# LMAT_AMT_V2.net
KiCad netlist of a schematic drawn in Altium Designer
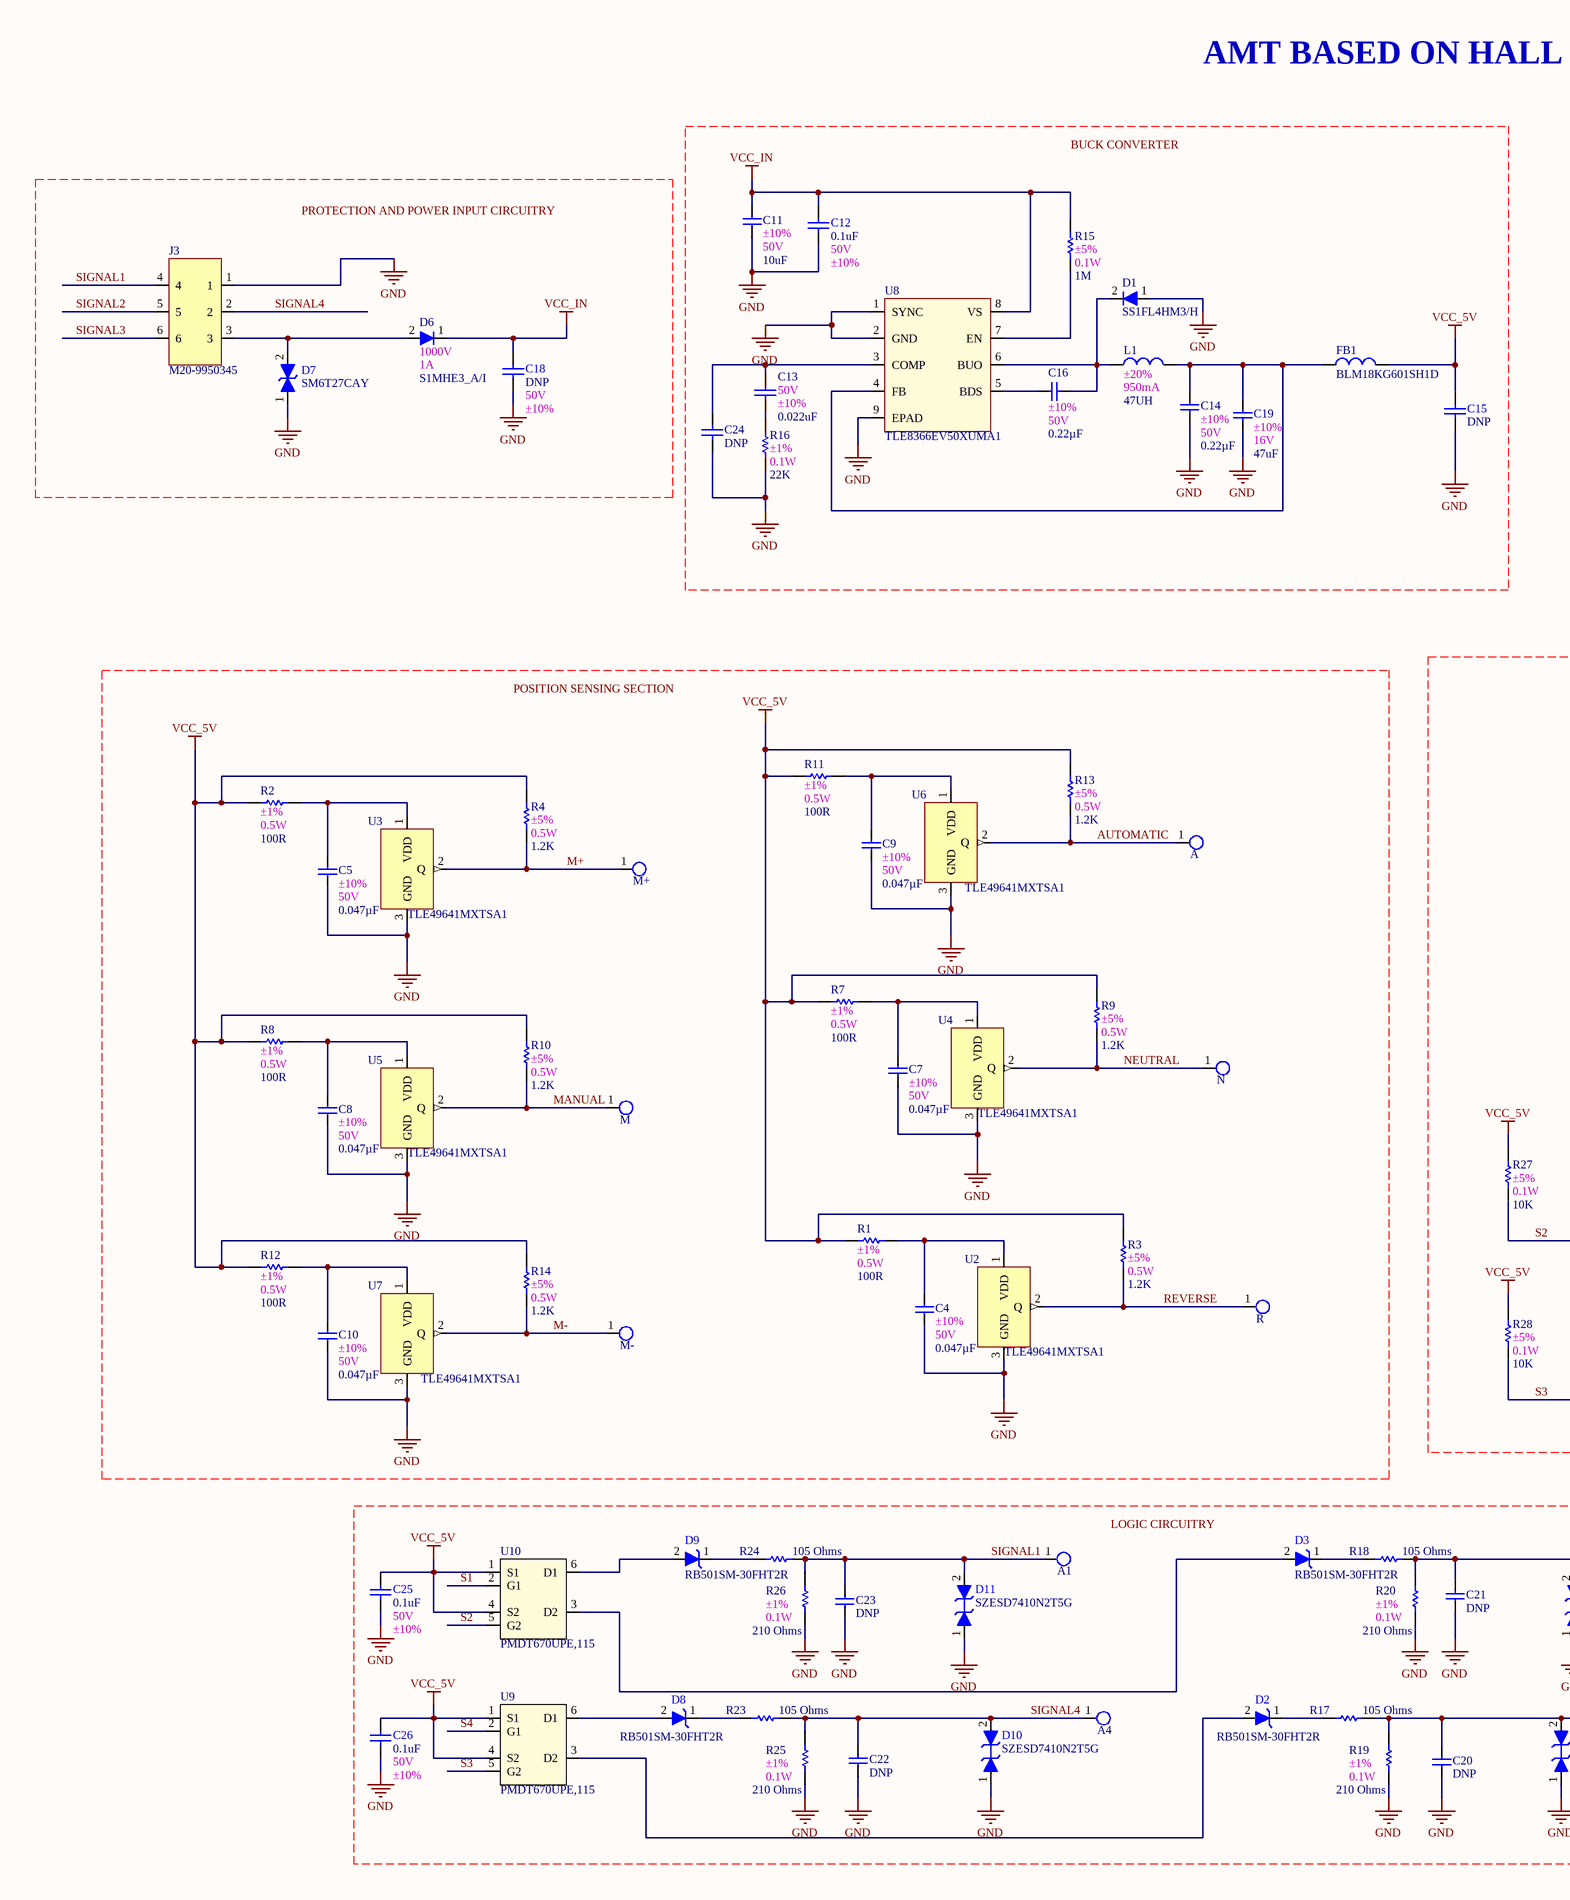
[diagram p0: LMAT_AMT_V2.SchDoc, left]
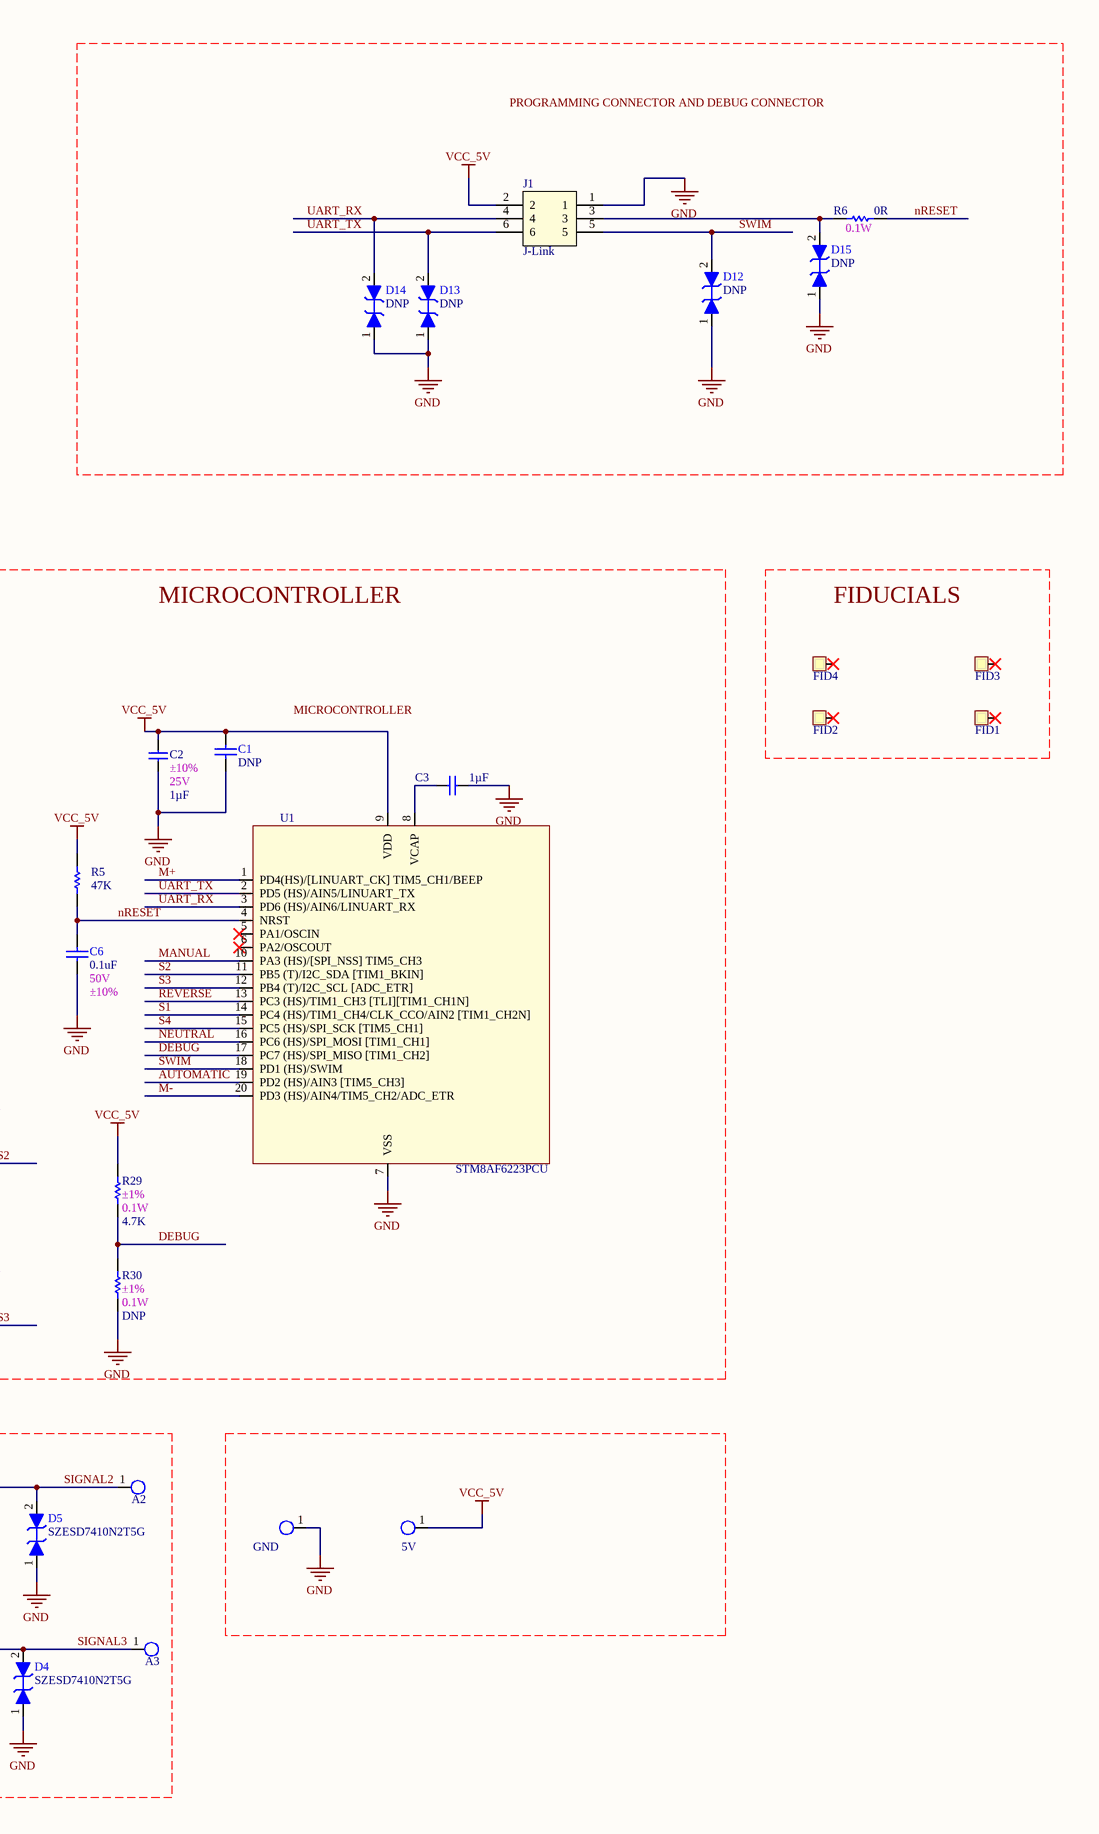
[diagram p1: LMAT_AMT_V2.SchDoc, right]

(export (version "E")
  (design (tool "Eeschema 10.0.6"))
  (components
    (comp (ref "5V")
      (value "Test Point- 35mil")
      (footprint "Integrated_Master_Library:TP_35M_DIA")
      (fields (field (name "INTERNAL PART NUMBER") "EMS-TP35MIL-S"))
      (libsource (lib "Integrated_Master_Library") (part "EMS-TP35MIL-S"))
    )
    (comp (ref "A")
      (value "Test Point- 35mil")
      (footprint "Integrated_Master_Library:TP_35M_DIA")
      (fields (field (name "INTERNAL PART NUMBER") "EMS-TP35MIL-S"))
      (libsource (lib "Integrated_Master_Library") (part "EMS-TP35MIL-S"))
    )
    (comp (ref "A1")
      (value "Test Point- 35mil")
      (footprint "Integrated_Master_Library:TP_35M_DIA")
      (fields (field (name "INTERNAL PART NUMBER") "EMS-TP35MIL-S"))
      (libsource (lib "Integrated_Master_Library") (part "EMS-TP35MIL-S"))
    )
    (comp (ref "A2")
      (value "Test Point- 35mil")
      (footprint "Integrated_Master_Library:TP_35M_DIA")
      (fields (field (name "INTERNAL PART NUMBER") "EMS-TP35MIL-S"))
      (libsource (lib "Integrated_Master_Library") (part "EMS-TP35MIL-S"))
    )
    (comp (ref "A3")
      (value "Test Point- 35mil")
      (footprint "Integrated_Master_Library:TP_35M_DIA")
      (fields (field (name "INTERNAL PART NUMBER") "EMS-TP35MIL-S"))
      (libsource (lib "Integrated_Master_Library") (part "EMS-TP35MIL-S"))
    )
    (comp (ref "A4")
      (value "Test Point- 35mil")
      (footprint "Integrated_Master_Library:TP_35M_DIA")
      (fields (field (name "INTERNAL PART NUMBER") "EMS-TP35MIL-S"))
      (libsource (lib "Integrated_Master_Library") (part "EMS-TP35MIL-S"))
    )
    (comp (ref "C1")
      (value "DNP")
      (footprint "SMDC0603")
      (description "CAP CER 0.1UF 50V 10% X7R 0603")
      (fields
        (field (name "MANUFACTURER PART NUMBER") "CGA3E2X7R1H104K080AA")
        (field (name "MANUFACTURER") "TDK Corporation")
      )
      (libsource (lib "Integrated_Master_Library") (part "ECA0U10K50V0-SC"))
    )
    (comp (ref "C2")
      (value "1µF")
      (footprint "Automobile-ML:SMDC0603")
      (description "CAP CER 1UF 25V X7R 0603")
      (fields
        (field (name "MANUFACTURER") "TDK Corporation")
        (field (name "VENDOR PART NUMBER") "445-173628-1-ND")
        (field (name "2ND AUXILIARY FIELD") "±10%")
        (field (name "1ST AUXILIARY FIELD") "25V")
      )
      (libsource (lib "Integrated_Master_Library (3)") (part "ECA1U00L25V0-SC"))
    )
    (comp (ref "C3")
      (value "1µF")
      (footprint "Automobile-ML:SMDC0603")
      (description "CAP CER 1UF 25V X7R 0603")
      (fields
        (field (name "MANUFACTURER") "TDK Corporation")
        (field (name "VENDOR PART NUMBER") "445-173628-1-ND")
      )
      (libsource (lib "Integrated_Master_Library (3)") (part "ECA1U00L25V0-SC"))
    )
    (comp (ref "C4")
      (value "0.047µF")
      (footprint "SMDC0603")
      (description "CAP CER 0.047UF 50V X7R 0603")
      (fields
        (field (name "MANUFACTURER") "TDK Corporation")
        (field (name "VENDOR PART NUMBER") "445-5664-1-ND")
        (field (name "2ND AUXILIARY FIELD") "±10%")
        (field (name "1ST AUXILIARY FIELD") "50V")
      )
      (libsource (lib "Integrated_Master_Library") (part "ECA47N0L50V-SC"))
    )
    (comp (ref "C5")
      (value "0.047µF")
      (footprint "SMDC0603")
      (description "CAP CER 0.047UF 50V X7R 0603")
      (fields
        (field (name "MANUFACTURER") "TDK Corporation")
        (field (name "VENDOR PART NUMBER") "445-5664-1-ND")
        (field (name "2ND AUXILIARY FIELD") "±10%")
        (field (name "1ST AUXILIARY FIELD") "50V")
      )
      (libsource (lib "Integrated_Master_Library") (part "ECA47N0L50V-SC"))
    )
    (comp (ref "C6")
      (value "0.1uF")
      (footprint "SMDC0603")
      (description "CAP CER 0.1UF 50V 10% X7R 0603")
      (fields
        (field (name "MANUFACTURER PART NUMBER") "CGA3E2X7R1H104K080AA")
        (field (name "MANUFACTURER") "TDK Corporation")
        (field (name "1ST AUXILIARY FIELD") "50V")
        (field (name "2ND AUXILIARY FIELD") "±10%")
      )
      (libsource (lib "Integrated_Master_Library") (part "ECA0U10K50V0-SC"))
    )
    (comp (ref "C7")
      (value "0.047µF")
      (footprint "SMDC0603")
      (description "CAP CER 0.047UF 50V X7R 0603")
      (fields
        (field (name "MANUFACTURER") "TDK Corporation")
        (field (name "VENDOR PART NUMBER") "445-5664-1-ND")
        (field (name "2ND AUXILIARY FIELD") "±10%")
        (field (name "1ST AUXILIARY FIELD") "50V")
      )
      (libsource (lib "Integrated_Master_Library") (part "ECA47N0L50V-SC"))
    )
    (comp (ref "C8")
      (value "0.047µF")
      (footprint "SMDC0603")
      (description "CAP CER 0.047UF 50V X7R 0603")
      (fields
        (field (name "MANUFACTURER") "TDK Corporation")
        (field (name "VENDOR PART NUMBER") "445-5664-1-ND")
        (field (name "2ND AUXILIARY FIELD") "±10%")
        (field (name "1ST AUXILIARY FIELD") "50V")
      )
      (libsource (lib "Integrated_Master_Library") (part "ECA47N0L50V-SC"))
    )
    (comp (ref "C9")
      (value "0.047µF")
      (footprint "SMDC0603")
      (description "CAP CER 0.047UF 50V X7R 0603")
      (fields
        (field (name "MANUFACTURER") "TDK Corporation")
        (field (name "VENDOR PART NUMBER") "445-5664-1-ND")
        (field (name "2ND AUXILIARY FIELD") "±10%")
        (field (name "1ST AUXILIARY FIELD") "50V")
      )
      (libsource (lib "Integrated_Master_Library") (part "ECA47N0L50V-SC"))
    )
    (comp (ref "C10")
      (value "0.047µF")
      (footprint "SMDC0603")
      (description "CAP CER 0.047UF 50V X7R 0603")
      (fields
        (field (name "MANUFACTURER") "TDK Corporation")
        (field (name "VENDOR PART NUMBER") "445-5664-1-ND")
        (field (name "2ND AUXILIARY FIELD") "±10%")
        (field (name "1ST AUXILIARY FIELD") "50V")
      )
      (libsource (lib "Integrated_Master_Library") (part "ECA47N0L50V-SC"))
    )
    (comp (ref "C11")
      (value "10uF")
      (footprint "SMDC1210")
      (description "CAP CER 10UF 50V X7R 1210")
      (fields
        (field (name "MANUFACTURER") "Taiyo Yuden")
        (field (name "VENDOR PART NUMBER") "587-6026-1-ND")
        (field (name "2ND AUXILIARY FIELD") "±10%")
        (field (name "1ST AUXILIARY FIELD") "50V")
      )
      (libsource (lib "Automobile-ML") (part "ECA10U0L50V0-SH"))
    )
    (comp (ref "C12")
      (value "0.1uF")
      (footprint "SMDC0603")
      (description "CAP CER 0.1UF 50V 10% X7R 0603")
      (fields
        (field (name "MANUFACTURER PART NUMBER") "CGA3E2X7R1H104K080AA")
        (field (name "MANUFACTURER") "TDK Corporation")
        (field (name "1ST AUXILIARY FIELD") "50V")
        (field (name "2ND AUXILIARY FIELD") "±10%")
      )
      (libsource (lib "Integrated_Master_Library") (part "ECA0U10K50V0-SC"))
    )
    (comp (ref "C13")
      (value "0.022uF")
      (footprint "SMDC0603")
      (description "CAP CER 0.022UF 50V 10% X7R 0603")
      (fields
        (field (name "MANUFACTURER PART NUMBER") "CGA3E2X7R1H223K080AA")
        (field (name "MANUFACTURER") "TDK Corporation")
        (field (name "1ST AUXILIARY FIELD") "50V")
        (field (name "2ND AUXILIARY FIELD") "±10%")
      )
      (libsource (lib "Integrated_Master_Library") (part "ECA0U022K50V0-SC"))
    )
    (comp (ref "C14")
      (value "0.22µF")
      (footprint "Automobile-ML:SMDC0603")
      (description "CAP CER 0.22UF 50V X7R 0603")
      (fields
        (field (name "MANUFACTURER") "Murata Electronics North America")
        (field (name "VENDOR PART NUMBER") "490-14410-1-ND")
        (field (name "2ND AUXILIARY FIELD") "±10%")
        (field (name "1ST AUXILIARY FIELD") "50V")
      )
      (libsource (lib "Integrated_Master_Library (3)") (part "ECA0U22L50V0-SC"))
    )
    (comp (ref "C15")
      (value "DNP")
      (footprint "SMDC0603")
      (description "CAP CER 0.1UF 50V 10% X7R 0603")
      (fields
        (field (name "MANUFACTURER PART NUMBER") "CGA3E2X7R1H104K080AA")
        (field (name "MANUFACTURER") "TDK Corporation")
      )
      (libsource (lib "Integrated_Master_Library") (part "ECA0U10K50V0-SC"))
    )
    (comp (ref "C16")
      (value "0.22µF")
      (footprint "SMDC0603")
      (description "CAP CER 0.22UF 50V X7R 0603")
      (fields
        (field (name "MANUFACTURER") "Murata Electronics North America")
        (field (name "VENDOR PART NUMBER") "490-14410-1-ND")
        (field (name "2ND AUXILIARY FIELD") "±10%")
        (field (name "1ST AUXILIARY FIELD") "50V")
      )
      (libsource (lib "Integrated_Master_Library") (part "ECA0U22L50V0-SC"))
    )
    (comp (ref "C18")
      (value "DNP")
      (footprint "SMDC0603")
      (description "CAP CER 0.1UF 50V 10% X7R 0603")
      (fields
        (field (name "MANUFACTURER PART NUMBER") "CGA3E2X7R1H104K080AA")
        (field (name "MANUFACTURER") "TDK Corporation")
        (field (name "1ST AUXILIARY FIELD") "50V")
        (field (name "2ND AUXILIARY FIELD") "±10%")
      )
      (libsource (lib "Integrated_Master_Library") (part "ECA0U10K50V0-SC"))
    )
    (comp (ref "C19")
      (value "47uF")
      (footprint "SMDC1210")
      (description "CAP CER 47UF 16V X6S 1210")
      (fields
        (field (name "MANUFACTURER") "Murata Electronics North America")
        (field (name "VENDOR PART NUMBER") "490-12494-1-ND")
        (field (name "2ND AUXILIARY FIELD") "±10%")
        (field (name "1ST AUXILIARY FIELD") "16V")
      )
      (libsource (lib "Automobile-ML") (part "ECA47U0L16V0-SH"))
    )
    (comp (ref "C20")
      (value "DNP")
      (footprint "SMDC0603")
      (description "CAP CER 10000PF 50V X8R 0603")
      (fields
        (field (name "MANUFACTURER") "TDK Corporation")
        (field (name "VENDOR PART NUMBER") "445-5892-1-ND")
      )
      (libsource (lib "Automobile-ML") (part "ECA0U01L50V0-SC"))
    )
    (comp (ref "C21")
      (value "DNP")
      (footprint "SMDC0603")
      (description "CAP CER 10000PF 50V X8R 0603")
      (fields
        (field (name "MANUFACTURER") "TDK Corporation")
        (field (name "VENDOR PART NUMBER") "445-5892-1-ND")
      )
      (libsource (lib "Automobile-ML") (part "ECA0U01L50V0-SC"))
    )
    (comp (ref "C22")
      (value "DNP")
      (footprint "SMDC0603")
      (description "CAP CER 10000PF 50V X8R 0603")
      (fields
        (field (name "MANUFACTURER") "TDK Corporation")
        (field (name "VENDOR PART NUMBER") "445-5892-1-ND")
      )
      (libsource (lib "Automobile-ML") (part "ECA0U01L50V0-SC"))
    )
    (comp (ref "C23")
      (value "DNP")
      (footprint "SMDC0603")
      (description "CAP CER 10000PF 50V X8R 0603")
      (fields
        (field (name "MANUFACTURER") "TDK Corporation")
        (field (name "VENDOR PART NUMBER") "445-5892-1-ND")
      )
      (libsource (lib "Automobile-ML") (part "ECA0U01L50V0-SC"))
    )
    (comp (ref "C24")
      (value "DNP")
      (footprint "SMDC0603")
      (description "CAP CER 0.022UF 50V 10% X7R 0603")
      (fields
        (field (name "MANUFACTURER PART NUMBER") "CGA3E2X7R1H223K080AA")
        (field (name "MANUFACTURER") "TDK Corporation")
      )
      (libsource (lib "Integrated_Master_Library") (part "ECA0U022K50V0-SC"))
    )
    (comp (ref "C25")
      (value "0.1uF")
      (footprint "SMDC0603")
      (description "CAP CER 0.1UF 50V 10% X7R 0603")
      (fields
        (field (name "MANUFACTURER PART NUMBER") "CGA3E2X7R1H104K080AA")
        (field (name "MANUFACTURER") "TDK Corporation")
        (field (name "1ST AUXILIARY FIELD") "50V")
        (field (name "2ND AUXILIARY FIELD") "±10%")
      )
      (libsource (lib "Integrated_Master_Library") (part "ECA0U10K50V0-SC"))
    )
    (comp (ref "C26")
      (value "0.1uF")
      (footprint "SMDC0603")
      (description "CAP CER 0.1UF 50V 10% X7R 0603")
      (fields
        (field (name "MANUFACTURER PART NUMBER") "CGA3E2X7R1H104K080AA")
        (field (name "MANUFACTURER") "TDK Corporation")
        (field (name "1ST AUXILIARY FIELD") "50V")
        (field (name "2ND AUXILIARY FIELD") "±10%")
      )
      (libsource (lib "Integrated_Master_Library") (part "ECA0U10K50V0-SC"))
    )
    (comp (ref "D1")
      (value "SS1FL4HM3/H")
      (footprint "Integrated_Master_Library:SODFL370X110-2N")
      (description "DIODE SCHOTTKY 40V 1A DO-219AB")
      (fields
        (field (name "MANUFACTURER") "Vishay Semiconductor Diodes Division")
        (field (name "INTERNAL PART NUMBER") "EDDVS1A0040V0-S")
      )
      (libsource (lib "Integrated_Master_Library (3)") (part "EDDVS1A0040V0-S"))
    )
    (comp (ref "D2")
      (value "RB501SM-30FHT2R")
      (footprint "Integrated_Master_Library:SOD1700X70N-V2")
      (description "Diode Schottky 30V 100mA Surface Mount EMD2")
      (fields
        (field (name "MANUFACTURER") "Rohm Semiconductor")
        (field (name "INTERNAL PART NUMBER") "EDDR0A1030V0-S")
      )
      (libsource (lib "Integrated_Master_Library (3)") (part "EDDR0A1030V0-S"))
    )
    (comp (ref "D3")
      (value "RB501SM-30FHT2R")
      (footprint "Integrated_Master_Library:SOD1700X70N-V2")
      (description "Diode Schottky 30V 100mA Surface Mount EMD2")
      (fields
        (field (name "MANUFACTURER") "Rohm Semiconductor")
        (field (name "INTERNAL PART NUMBER") "EDDR0A1030V0-S")
      )
      (libsource (lib "Integrated_Master_Library (3)") (part "EDDR0A1030V0-S"))
    )
    (comp (ref "D4")
      (value "SZESD7410N2T5G")
      (footprint "DFN65P100X65X45-2N")
      (description "TVS DIODE 8V 20V 2X2DFN")
      (fields
        (field (name "MANUFACTURER") "ON Semiconductor")
        (field (name "INTERNAL PART NUMBER") "EDDOS16A010V0-S")
      )
      (libsource (lib "Automobile-ML") (part "EDDOS16A010V0-S"))
    )
    (comp (ref "D5")
      (value "SZESD7410N2T5G")
      (footprint "DFN65P100X65X45-2N")
      (description "TVS DIODE 8V 20V 2X2DFN")
      (fields
        (field (name "MANUFACTURER") "ON Semiconductor")
        (field (name "INTERNAL PART NUMBER") "EDDOS16A010V0-S")
      )
      (libsource (lib "Automobile-ML") (part "EDDOS16A010V0-S"))
    )
    (comp (ref "D6")
      (value "S1MHE3_A/I")
      (footprint "Integrated_Master_Library:DIOM4227X23N-2N")
      (description "DIODE GEN PURP 1KV 1A DO214AC")
      (fields
        (field (name "MANUFACTURER") "Vishay Semiconductor Diodes Division")
        (field (name "INTERNAL PART NUMBER") "EDDVS1A001000V-S")
        (field (name "1ST AUXILIARY FIELD") "1000V")
        (field (name "2ND AUXILIARY FIELD") "1A")
      )
      (libsource (lib "Integrated_Master_Library") (part "EDDVS1A001000V-S"))
    )
    (comp (ref "D7")
      (value "SM6T27CAY")
      (footprint "DIOM4336X26B")
      (description "TVS DIODE 23.1V 48.3V SMB")
      (fields
        (field (name "MANUFACTURER") "STMicroelectronics")
        (field (name "INTERNAL PART NUMBER") "EDDST83A025V7-S")
      )
      (libsource (lib "Integrated_Master_Library") (part "EDDST83A025V7-S"))
    )
    (comp (ref "D8")
      (value "RB501SM-30FHT2R")
      (footprint "Integrated_Master_Library:SOD1700X70N-V2")
      (description "Diode Schottky 30V 100mA Surface Mount EMD2")
      (fields
        (field (name "MANUFACTURER") "Rohm Semiconductor")
        (field (name "INTERNAL PART NUMBER") "EDDR0A1030V0-S")
      )
      (libsource (lib "Integrated_Master_Library (3)") (part "EDDR0A1030V0-S"))
    )
    (comp (ref "D9")
      (value "RB501SM-30FHT2R")
      (footprint "Integrated_Master_Library:SOD1700X70N-V2")
      (description "Diode Schottky 30V 100mA Surface Mount EMD2")
      (fields
        (field (name "MANUFACTURER") "Rohm Semiconductor")
        (field (name "INTERNAL PART NUMBER") "EDDR0A1030V0-S")
      )
      (libsource (lib "Integrated_Master_Library (3)") (part "EDDR0A1030V0-S"))
    )
    (comp (ref "D10")
      (value "SZESD7410N2T5G")
      (footprint "DFN65P100X65X45-2N")
      (description "TVS DIODE 8V 20V 2X2DFN")
      (fields
        (field (name "MANUFACTURER") "ON Semiconductor")
        (field (name "INTERNAL PART NUMBER") "EDDOS16A010V0-S")
      )
      (libsource (lib "Automobile-ML") (part "EDDOS16A010V0-S"))
    )
    (comp (ref "D11")
      (value "SZESD7410N2T5G")
      (footprint "DFN65P100X65X45-2N")
      (description "TVS DIODE 8V 20V 2X2DFN")
      (fields
        (field (name "MANUFACTURER") "ON Semiconductor")
        (field (name "INTERNAL PART NUMBER") "EDDOS16A010V0-S")
      )
      (libsource (lib "Automobile-ML") (part "EDDOS16A010V0-S"))
    )
    (comp (ref "D12")
      (value "DNP")
      (footprint "DFN65P100X65X45-2N")
      (description "TVS DIODE 8V 20V 2X2DFN")
      (fields
        (field (name "MANUFACTURER PART NUMBER") "SZESD7410N2T5G")
        (field (name "MANUFACTURER") "ON Semiconductor")
      )
      (libsource (lib "Automobile-ML") (part "EDDOS16A010V0-S"))
    )
    (comp (ref "D13")
      (value "DNP")
      (footprint "DFN65P100X65X45-2N")
      (description "TVS DIODE 8V 20V 2X2DFN")
      (fields
        (field (name "MANUFACTURER PART NUMBER") "SZESD7410N2T5G")
        (field (name "MANUFACTURER") "ON Semiconductor")
      )
      (libsource (lib "Automobile-ML") (part "EDDOS16A010V0-S"))
    )
    (comp (ref "D14")
      (value "DNP")
      (footprint "DFN65P100X65X45-2N")
      (description "TVS DIODE 8V 20V 2X2DFN")
      (fields
        (field (name "MANUFACTURER PART NUMBER") "SZESD7410N2T5G")
        (field (name "MANUFACTURER") "ON Semiconductor")
      )
      (libsource (lib "Automobile-ML") (part "EDDOS16A010V0-S"))
    )
    (comp (ref "D15")
      (value "DNP")
      (footprint "DFN65P100X65X45-2N")
      (description "TVS DIODE 8V 20V 2X2DFN")
      (fields
        (field (name "MANUFACTURER PART NUMBER") "SZESD7410N2T5G")
        (field (name "MANUFACTURER") "ON Semiconductor")
      )
      (libsource (lib "Automobile-ML") (part "EDDOS16A010V0-S"))
    )
    (comp (ref "FB1")
      (value "BLM18KG601SH1D")
      (footprint "Integrated_Master_Library:SMDL0603")
      (description "FERRITE BEAD 600 OHM 0603 1LN")
      (fields
        (field (name "MANUFACTURER") "Murata Electronics North America")
        (field (name "VENDOR PART NUMBER") "490-13259-1-ND")
      )
      (libsource (lib "Automobile-ML") (part "EIN600R1A30-S"))
    )
    (comp (ref "FID1")
      (value "FID40X40")
      (footprint "FID40X40")
      (libsource (lib "Integrated_Master_Library") (part "FID_40X40"))
    )
    (comp (ref "FID2")
      (value "FID40X40")
      (footprint "FID40X40")
      (libsource (lib "Integrated_Master_Library") (part "FID_40X40"))
    )
    (comp (ref "FID3")
      (value "FID40X40")
      (footprint "FID40X40")
      (libsource (lib "Integrated_Master_Library") (part "FID_40X40"))
    )
    (comp (ref "FID4")
      (value "FID40X40")
      (footprint "FID40X40")
      (libsource (lib "Integrated_Master_Library") (part "FID_40X40"))
    )
    (comp (ref "GND")
      (value "Test Point- 35mil")
      (footprint "Integrated_Master_Library:TP_35M_DIA")
      (fields (field (name "INTERNAL PART NUMBER") "EMS-TP35MIL-S"))
      (libsource (lib "Integrated_Master_Library") (part "EMS-TP35MIL-S"))
    )
    (comp (ref "J1")
      (value "J-LINK 6-PIN NEEDLE ADAPTER")
      (footprint "PRG_8.06.16 J-LINK 6-PIN NEEDLE ADAPTER")
      (fields
        (field (name "INTERNAL PART NUMBER") "EMS-8.06.16 J-LINK 6-PIN NEEDLE ADAPTER")
        (field (name "MANUFACTURER") "Segger Microcontroller Systems")
        (field (name "VENDOR PART NUMBER") "899-1051-ND")
        (field (name "1ST AUXILIARY FIELD") "J-Link")
      )
      (libsource (lib "Integrated_Master_Library") (part "EMS-8.06.16 J-LINK 6-PIN NEEDLE ADAPTER"))
    )
    (comp (ref "J3")
      (value "CONN HEADER R/A 6POS 2.54MM")
      (footprint "HDRRA6W86P254_2X3_1344X254X528P_Modified")
      (fields
        (field (name "MANUFACTURER") "Harwin Inc.")
        (field (name "INTERNAL PART NUMBER") "ECN-M20-9950345-0003-0060")
        (field (name "VENDOR PART NUMBER") "952-2092-ND")
        (field (name "MANUFACTURER PART NUMBER") "M20-9950345")
      )
      (libsource (lib "Automobile-ML") (part "ECN-M20-9950345-0003-0060"))
    )
    (comp (ref "L1")
      (value "47UH")
      (footprint "INDC4949X310N")
      (description "FIXED IND 47UH 700MA 422.5 MOHM")
      (fields
        (field (name "MANUFACTURER") "Taiyo Yuden")
        (field (name "VENDOR PART NUMBER") "587-3604-1-ND")
        (field (name "2ND AUXILIARY FIELD") "±20%")
        (field (name "1ST AUXILIARY FIELD") "950mA")
      )
      (libsource (lib "Automobile-ML") (part "EIN47U0N950M-S"))
    )
    (comp (ref "M")
      (value "Test Point- 35mil")
      (footprint "Integrated_Master_Library:TP_35M_DIA")
      (fields (field (name "INTERNAL PART NUMBER") "EMS-TP35MIL-S"))
      (libsource (lib "Integrated_Master_Library") (part "EMS-TP35MIL-S"))
    )
    (comp (ref "M+")
      (value "Test Point- 35mil")
      (footprint "Integrated_Master_Library:TP_35M_DIA")
      (fields (field (name "INTERNAL PART NUMBER") "EMS-TP35MIL-S"))
      (libsource (lib "Integrated_Master_Library") (part "EMS-TP35MIL-S"))
    )
    (comp (ref "M-")
      (value "Test Point- 35mil")
      (footprint "Integrated_Master_Library:TP_35M_DIA")
      (fields (field (name "INTERNAL PART NUMBER") "EMS-TP35MIL-S"))
      (libsource (lib "Integrated_Master_Library") (part "EMS-TP35MIL-S"))
    )
    (comp (ref "N")
      (value "Test Point- 35mil")
      (footprint "Integrated_Master_Library:TP_35M_DIA")
      (fields (field (name "INTERNAL PART NUMBER") "EMS-TP35MIL-S"))
      (libsource (lib "Integrated_Master_Library") (part "EMS-TP35MIL-S"))
    )
    (comp (ref "R")
      (value "Test Point- 35mil")
      (footprint "Integrated_Master_Library:TP_35M_DIA")
      (fields (field (name "INTERNAL PART NUMBER") "EMS-TP35MIL-S"))
      (libsource (lib "Integrated_Master_Library") (part "EMS-TP35MIL-S"))
    )
    (comp (ref "R1")
      (value "100R")
      (footprint "SMDR0805")
      (description "RES SMD 100 OHM 1% 1/2W 0805")
      (fields
        (field (name "MANUFACTURER PART NUMBER") "ERJ-P06F1000V")
        (field (name "MANUFACTURER") "Panasonic Electronic Components")
        (field (name "2ND AUXILIARY FIELD") "±1%")
        (field (name "1ST AUXILIARY FIELD") "0.5W")
      )
      (libsource (lib "Automobile-ML") (part "ERE100RG120-SE"))
    )
    (comp (ref "R2")
      (value "100R")
      (footprint "SMDR0805")
      (description "RES SMD 100 OHM 1% 1/2W 0805")
      (fields
        (field (name "MANUFACTURER PART NUMBER") "ERJ-P06F1000V")
        (field (name "MANUFACTURER") "Panasonic Electronic Components")
        (field (name "2ND AUXILIARY FIELD") "±1%")
        (field (name "1ST AUXILIARY FIELD") "0.5W")
      )
      (libsource (lib "Automobile-ML") (part "ERE100RG120-SE"))
    )
    (comp (ref "R3")
      (value "1.2K")
      (footprint "SMDR0805")
      (description "RES SMD 1.2K OHM 5% 1/2W 0805")
      (fields
        (field (name "MANUFACTURER") "Panasonic Electronic Components")
        (field (name "VENDOR PART NUMBER") "P1.2KADCT-ND")
        (field (name "2ND AUXILIARY FIELD") "±5%")
        (field (name "1ST AUXILIARY FIELD") "0.5W")
      )
      (libsource (lib "Integrated_Master_Library") (part "ERE1K20G102-SE"))
    )
    (comp (ref "R4")
      (value "1.2K")
      (footprint "SMDR0805")
      (description "RES SMD 1.2K OHM 5% 1/2W 0805")
      (fields
        (field (name "MANUFACTURER") "Panasonic Electronic Components")
        (field (name "VENDOR PART NUMBER") "P1.2KADCT-ND")
        (field (name "2ND AUXILIARY FIELD") "±5%")
        (field (name "1ST AUXILIARY FIELD") "0.5W")
      )
      (libsource (lib "Integrated_Master_Library") (part "ERE1K20G102-SE"))
    )
    (comp (ref "R5")
      (value "47K")
      (footprint "Automobile-ML:SMDR0603")
      (description "RES SMD 47K OHM 1% 1/10W 0603")
      (fields (field (name "MANUFACTURER") "Yageo") (field (name "VENDOR PART NUMBER") "YAG2129CT-ND"))
      (libsource (lib "Integrated_Master_Library (3)") (part "ERE47K0G110-SC"))
    )
    (comp (ref "R6")
      (value "0R")
      (footprint "SMDR0603")
      (description "RES SMD 0.0OHM JUMPER 1/10W 0603")
      (fields
        (field (name "MANUFACTURER PART NUMBER") "ERJ-3GEY0R00V")
        (field (name "MANUFACTURER") "Panasonic Electronic Components")
        (field (name "1ST AUXILIARY FIELD") "0.1W")
      )
      (libsource (lib "Integrated_Master_Library") (part "ERE0R00110-SC"))
    )
    (comp (ref "R7")
      (value "100R")
      (footprint "SMDR0805")
      (description "RES SMD 100 OHM 1% 1/2W 0805")
      (fields
        (field (name "MANUFACTURER PART NUMBER") "ERJ-P06F1000V")
        (field (name "MANUFACTURER") "Panasonic Electronic Components")
        (field (name "2ND AUXILIARY FIELD") "±1%")
        (field (name "1ST AUXILIARY FIELD") "0.5W")
      )
      (libsource (lib "Automobile-ML") (part "ERE100RG120-SE"))
    )
    (comp (ref "R8")
      (value "100R")
      (footprint "SMDR0805")
      (description "RES SMD 100 OHM 1% 1/2W 0805")
      (fields
        (field (name "MANUFACTURER PART NUMBER") "ERJ-P06F1000V")
        (field (name "MANUFACTURER") "Panasonic Electronic Components")
        (field (name "2ND AUXILIARY FIELD") "±1%")
        (field (name "1ST AUXILIARY FIELD") "0.5W")
      )
      (libsource (lib "Automobile-ML") (part "ERE100RG120-SE"))
    )
    (comp (ref "R9")
      (value "1.2K")
      (footprint "SMDR0805")
      (description "RES SMD 1.2K OHM 5% 1/2W 0805")
      (fields
        (field (name "MANUFACTURER") "Panasonic Electronic Components")
        (field (name "VENDOR PART NUMBER") "P1.2KADCT-ND")
        (field (name "2ND AUXILIARY FIELD") "±5%")
        (field (name "1ST AUXILIARY FIELD") "0.5W")
      )
      (libsource (lib "Integrated_Master_Library") (part "ERE1K20G102-SE"))
    )
    (comp (ref "R10")
      (value "1.2K")
      (footprint "SMDR0805")
      (description "RES SMD 1.2K OHM 5% 1/2W 0805")
      (fields
        (field (name "MANUFACTURER") "Panasonic Electronic Components")
        (field (name "VENDOR PART NUMBER") "P1.2KADCT-ND")
        (field (name "2ND AUXILIARY FIELD") "±5%")
        (field (name "1ST AUXILIARY FIELD") "0.5W")
      )
      (libsource (lib "Integrated_Master_Library") (part "ERE1K20G102-SE"))
    )
    (comp (ref "R11")
      (value "100R")
      (footprint "SMDR0805")
      (description "RES SMD 100 OHM 1% 1/2W 0805")
      (fields
        (field (name "MANUFACTURER PART NUMBER") "ERJ-P06F1000V")
        (field (name "MANUFACTURER") "Panasonic Electronic Components")
        (field (name "2ND AUXILIARY FIELD") "±1%")
        (field (name "1ST AUXILIARY FIELD") "0.5W")
      )
      (libsource (lib "Automobile-ML") (part "ERE100RG120-SE"))
    )
    (comp (ref "R12")
      (value "100R")
      (footprint "SMDR0805")
      (description "RES SMD 100 OHM 1% 1/2W 0805")
      (fields
        (field (name "MANUFACTURER PART NUMBER") "ERJ-P06F1000V")
        (field (name "MANUFACTURER") "Panasonic Electronic Components")
        (field (name "2ND AUXILIARY FIELD") "±1%")
        (field (name "1ST AUXILIARY FIELD") "0.5W")
      )
      (libsource (lib "Automobile-ML") (part "ERE100RG120-SE"))
    )
    (comp (ref "R13")
      (value "1.2K")
      (footprint "SMDR0805")
      (description "RES SMD 1.2K OHM 5% 1/2W 0805")
      (fields
        (field (name "MANUFACTURER") "Panasonic Electronic Components")
        (field (name "VENDOR PART NUMBER") "P1.2KADCT-ND")
        (field (name "2ND AUXILIARY FIELD") "±5%")
        (field (name "1ST AUXILIARY FIELD") "0.5W")
      )
      (libsource (lib "Integrated_Master_Library") (part "ERE1K20G102-SE"))
    )
    (comp (ref "R14")
      (value "1.2K")
      (footprint "SMDR0805")
      (description "RES SMD 1.2K OHM 5% 1/2W 0805")
      (fields
        (field (name "MANUFACTURER") "Panasonic Electronic Components")
        (field (name "VENDOR PART NUMBER") "P1.2KADCT-ND")
        (field (name "2ND AUXILIARY FIELD") "±5%")
        (field (name "1ST AUXILIARY FIELD") "0.5W")
      )
      (libsource (lib "Integrated_Master_Library") (part "ERE1K20G102-SE"))
    )
    (comp (ref "R15")
      (value "1M")
      (footprint "SMDR0603")
      (description "RES SMD 1M OHM 5% 1/10W 0603")
      (fields
        (field (name "MANUFACTURER") "Vishay Dale")
        (field (name "VENDOR PART NUMBER") "541-2216-1-ND")
        (field (name "2ND AUXILIARY FIELD") "±5%")
        (field (name "1ST AUXILIARY FIELD") "0.1W")
      )
      (libsource (lib "Automobile-ML") (part "ERE1M00K110-SC"))
    )
    (comp (ref "R16")
      (value "22K")
      (footprint "SMDR0603")
      (description "RES SMD 22K OHM 1% 1/10W 0603")
      (fields
        (field (name "MANUFACTURER") "Panasonic Electronic Components")
        (field (name "VENDOR PART NUMBER") "P22.0KHCT-ND")
        (field (name "2ND AUXILIARY FIELD") "±1%")
        (field (name "1ST AUXILIARY FIELD") "0.1W")
      )
      (libsource (lib "Automobile-ML") (part "ERE22K0G110-SC"))
    )
    (comp (ref "R17")
      (value "105 Ohms")
      (footprint "SMDR0603")
      (description "RES SMD 105 OHM 1% 1/10W 0603")
      (fields
        (field (name "MANUFACTURER") "Panasonic Electronic Components")
        (field (name "VENDOR PART NUMBER") "P105HCT-ND")
      )
      (libsource (lib "Automobile-ML") (part "ERE105RG110-SC"))
    )
    (comp (ref "R18")
      (value "105 Ohms")
      (footprint "SMDR0603")
      (description "RES SMD 105 OHM 1% 1/10W 0603")
      (fields
        (field (name "MANUFACTURER") "Panasonic Electronic Components")
        (field (name "VENDOR PART NUMBER") "P105HCT-ND")
      )
      (libsource (lib "Automobile-ML") (part "ERE105RG110-SC"))
    )
    (comp (ref "R19")
      (value "210 Ohms")
      (footprint "SMDR0603")
      (description "RES SMD 210 OHM 1% 1/10W 0603")
      (fields
        (field (name "MANUFACTURER") "Panasonic Electronic Components")
        (field (name "VENDOR PART NUMBER") "P210HCT-ND")
        (field (name "2ND AUXILIARY FIELD") "±1%")
        (field (name "1ST AUXILIARY FIELD") "0.1W")
      )
      (libsource (lib "Automobile-ML") (part "ERE210RG110-SC"))
    )
    (comp (ref "R20")
      (value "210 Ohms")
      (footprint "SMDR0603")
      (description "RES SMD 210 OHM 1% 1/10W 0603")
      (fields
        (field (name "MANUFACTURER") "Panasonic Electronic Components")
        (field (name "VENDOR PART NUMBER") "P210HCT-ND")
        (field (name "2ND AUXILIARY FIELD") "±1%")
        (field (name "1ST AUXILIARY FIELD") "0.1W")
      )
      (libsource (lib "Automobile-ML") (part "ERE210RG110-SC"))
    )
    (comp (ref "R23")
      (value "105 Ohms")
      (footprint "SMDR0603")
      (description "RES SMD 105 OHM 1% 1/10W 0603")
      (fields
        (field (name "MANUFACTURER") "Panasonic Electronic Components")
        (field (name "VENDOR PART NUMBER") "P105HCT-ND")
      )
      (libsource (lib "Automobile-ML") (part "ERE105RG110-SC"))
    )
    (comp (ref "R24")
      (value "105 Ohms")
      (footprint "SMDR0603")
      (description "RES SMD 105 OHM 1% 1/10W 0603")
      (fields
        (field (name "MANUFACTURER") "Panasonic Electronic Components")
        (field (name "VENDOR PART NUMBER") "P105HCT-ND")
      )
      (libsource (lib "Automobile-ML") (part "ERE105RG110-SC"))
    )
    (comp (ref "R25")
      (value "210 Ohms")
      (footprint "SMDR0603")
      (description "RES SMD 210 OHM 1% 1/10W 0603")
      (fields
        (field (name "MANUFACTURER") "Panasonic Electronic Components")
        (field (name "VENDOR PART NUMBER") "P210HCT-ND")
        (field (name "2ND AUXILIARY FIELD") "±1%")
        (field (name "1ST AUXILIARY FIELD") "0.1W")
      )
      (libsource (lib "Automobile-ML") (part "ERE210RG110-SC"))
    )
    (comp (ref "R26")
      (value "210 Ohms")
      (footprint "SMDR0603")
      (description "RES SMD 210 OHM 1% 1/10W 0603")
      (fields
        (field (name "MANUFACTURER") "Panasonic Electronic Components")
        (field (name "VENDOR PART NUMBER") "P210HCT-ND")
        (field (name "2ND AUXILIARY FIELD") "±1%")
        (field (name "1ST AUXILIARY FIELD") "0.1W")
      )
      (libsource (lib "Automobile-ML") (part "ERE210RG110-SC"))
    )
    (comp (ref "R27")
      (value "10K")
      (footprint "Automobile-ML:SMDR0402")
      (description "RES SMD 10K OHM 5% 1/10W 0402")
      (fields
        (field (name "MANUFACTURER") "Panasonic Electronic Components")
        (field (name "VENDOR PART NUMBER") "P10KJCT-ND")
        (field (name "2ND AUXILIARY FIELD") "±5%")
        (field (name "1ST AUXILIARY FIELD") "0.1W")
      )
      (libsource (lib "Automobile-ML") (part "ERE10K0K110-SB"))
    )
    (comp (ref "R28")
      (value "10K")
      (footprint "Automobile-ML:SMDR0402")
      (description "RES SMD 10K OHM 5% 1/10W 0402")
      (fields
        (field (name "MANUFACTURER") "Panasonic Electronic Components")
        (field (name "VENDOR PART NUMBER") "P10KJCT-ND")
        (field (name "2ND AUXILIARY FIELD") "±5%")
        (field (name "1ST AUXILIARY FIELD") "0.1W")
      )
      (libsource (lib "Automobile-ML") (part "ERE10K0K110-SB"))
    )
    (comp (ref "R29")
      (value "4.7K")
      (footprint "SMDR0402")
      (description "RES SMD 4.7K OHM 1% 1/10W 0402")
      (fields
        (field (name "MANUFACTURER") "Panasonic Electronic Components")
        (field (name "VENDOR PART NUMBER") "P4.70KLCT-ND")
        (field (name "2ND AUXILIARY FIELD") "±1%")
        (field (name "1ST AUXILIARY FIELD") "0.1W")
      )
      (libsource (lib "Automobile-ML") (part "ERE4K70G110-SB"))
    )
    (comp (ref "R30")
      (value "DNP")
      (footprint "SMDR0402")
      (description "RES SMD 4.7K OHM 1% 1/10W 0402")
      (fields
        (field (name "MANUFACTURER") "Panasonic Electronic Components")
        (field (name "VENDOR PART NUMBER") "P4.70KLCT-ND")
        (field (name "2ND AUXILIARY FIELD") "±1%")
        (field (name "1ST AUXILIARY FIELD") "0.1W")
      )
      (libsource (lib "Automobile-ML") (part "ERE4K70G110-SB"))
    )
    (comp (ref "U1")
      (value "STM8AF6223PCU")
      (footprint "Automobile-ML:SOP65P640X120-20N")
      (description "IC MCU 8BIT 8KB FLASH 20TSSOP")
      (fields
        (field (name "MANUFACTURER") "STMicroelectronics")
        (field (name "INTERNAL PART NUMBER") "EICSTMTSSOP-20-1691")
      )
      (libsource (lib "Integrated_Master_Library (3)") (part "EICSTMTSSOP-20-1691"))
    )
    (comp (ref "U2")
      (value "TLE49641MXTSA1")
      (footprint "Integrated_Master_Library:SOT95P248X115-3N")
      (description "MAGNETIC SWITCH UNIPOLAR SOT23-3")
      (fields
        (field (name "MANUFACTURER") "Infineon Technologies")
        (field (name "VENDOR PART NUMBER") "TLE49641MXTSA1CT-ND")
      )
      (libsource (lib "Integrated_Master_Library") (part "EICITSOT23-3-1528"))
    )
    (comp (ref "U3")
      (value "TLE49641MXTSA1")
      (footprint "Integrated_Master_Library:SOT95P248X115-3N")
      (description "MAGNETIC SWITCH UNIPOLAR SOT23-3")
      (fields
        (field (name "MANUFACTURER") "Infineon Technologies")
        (field (name "VENDOR PART NUMBER") "TLE49641MXTSA1CT-ND")
      )
      (libsource (lib "Integrated_Master_Library") (part "EICITSOT23-3-1528"))
    )
    (comp (ref "U4")
      (value "TLE49641MXTSA1")
      (footprint "Integrated_Master_Library:SOT95P248X115-3N")
      (description "MAGNETIC SWITCH UNIPOLAR SOT23-3")
      (fields
        (field (name "MANUFACTURER") "Infineon Technologies")
        (field (name "VENDOR PART NUMBER") "TLE49641MXTSA1CT-ND")
      )
      (libsource (lib "Integrated_Master_Library") (part "EICITSOT23-3-1528"))
    )
    (comp (ref "U5")
      (value "TLE49641MXTSA1")
      (footprint "Integrated_Master_Library:SOT95P248X115-3N")
      (description "MAGNETIC SWITCH UNIPOLAR SOT23-3")
      (fields
        (field (name "MANUFACTURER") "Infineon Technologies")
        (field (name "VENDOR PART NUMBER") "TLE49641MXTSA1CT-ND")
      )
      (libsource (lib "Integrated_Master_Library") (part "EICITSOT23-3-1528"))
    )
    (comp (ref "U6")
      (value "TLE49641MXTSA1")
      (footprint "Integrated_Master_Library:SOT95P248X115-3N")
      (description "MAGNETIC SWITCH UNIPOLAR SOT23-3")
      (fields
        (field (name "MANUFACTURER") "Infineon Technologies")
        (field (name "VENDOR PART NUMBER") "TLE49641MXTSA1CT-ND")
      )
      (libsource (lib "Integrated_Master_Library") (part "EICITSOT23-3-1528"))
    )
    (comp (ref "U7")
      (value "TLE49641MXTSA1")
      (footprint "Integrated_Master_Library:SOT95P248X115-3N")
      (description "MAGNETIC SWITCH UNIPOLAR SOT23-3")
      (fields
        (field (name "MANUFACTURER") "Infineon Technologies")
        (field (name "VENDOR PART NUMBER") "TLE49641MXTSA1CT-ND")
      )
      (libsource (lib "Integrated_Master_Library") (part "EICITSOT23-3-1528"))
    )
    (comp (ref "U8")
      (value "TLE8366EV50XUMA1")
      (footprint "SOIC127P600X170_HS-9N")
      (description "IC REG BUCK 5V 1.8A 8DSO")
      (fields
        (field (name "MANUFACTURER") "Infineon Technologies")
        (field (name "INTERNAL PART NUMBER") "EICITSOIC-08-0001")
      )
      (libsource (lib "Automobile-ML") (part "EICITSOIC-08-0001"))
    )
    (comp (ref "U9")
      (value "PMDT670UPE,115")
      (footprint "SOTFL50P160X60-6N")
      (description "MOSFET 2P-CH 20V 0.55A SOT666")
      (fields
        (field (name "MANUFACTURER") "Nexperia USA Inc.")
        (field (name "INTERNAL PART NUMBER") "EICNUSOT666-06-0004")
      )
      (libsource (lib "Automobile-ML") (part "EICNUSOT666-06-0004"))
    )
    (comp (ref "U10")
      (value "PMDT670UPE,115")
      (footprint "SOTFL50P160X60-6N")
      (description "MOSFET 2P-CH 20V 0.55A SOT666")
      (fields
        (field (name "MANUFACTURER") "Nexperia USA Inc.")
        (field (name "INTERNAL PART NUMBER") "EICNUSOT666-06-0004")
      )
      (libsource (lib "Automobile-ML") (part "EICNUSOT666-06-0004"))
    )
  )
  (nets
    (net (code "1") (name "/AUTOMATIC") (class "Default")
      (node (ref "A") (pin "1") (pinfunction "1_1") (pintype "passive"))
      (node (ref "R13") (pin "2") (pinfunction "2_2") (pintype "passive"))
      (node (ref "U1") (pin "19") (pinfunction "PD2_(HS)/AIN3_[TIM5_CH3]_19") (pintype "passive"))
      (node (ref "U6") (pin "2") (pinfunction "Q_2") (pintype "output"))
    )
    (net (code "2") (name "/DEBUG") (class "Default")
      (node (ref "R29") (pin "1") (pinfunction "1_1") (pintype "passive"))
      (node (ref "R30") (pin "2") (pinfunction "2_2") (pintype "passive"))
      (node (ref "U1") (pin "17") (pinfunction "PC7_(HS)/SPI_MISO_[TIM1_CH2]_17") (pintype "passive"))
    )
    (net (code "3") (name "/M+") (class "Default")
      (node (ref "M+") (pin "1") (pinfunction "1_1") (pintype "passive"))
      (node (ref "R4") (pin "2") (pinfunction "2_2") (pintype "passive"))
      (node (ref "U1") (pin "1") (pinfunction "PD4(HS)/[LINUART_CK]_TIM5_CH1/BEEP_1") (pintype "passive"))
      (node (ref "U3") (pin "2") (pinfunction "Q_2") (pintype "output"))
    )
    (net (code "4") (name "/M-") (class "Default")
      (node (ref "M-") (pin "1") (pinfunction "1_1") (pintype "passive"))
      (node (ref "R14") (pin "2") (pinfunction "2_2") (pintype "passive"))
      (node (ref "U1") (pin "20") (pinfunction "PD3_(HS)/AIN4/TIM5_CH2/ADC_ETR_20") (pintype "passive"))
      (node (ref "U7") (pin "2") (pinfunction "Q_2") (pintype "output"))
    )
    (net (code "5") (name "/MANUAL") (class "Default")
      (node (ref "M") (pin "1") (pinfunction "1_1") (pintype "passive"))
      (node (ref "R10") (pin "2") (pinfunction "2_2") (pintype "passive"))
      (node (ref "U1") (pin "10") (pinfunction "PA3_(HS)/[SPI_NSS]_TIM5_CH3_10") (pintype "passive"))
      (node (ref "U5") (pin "2") (pinfunction "Q_2") (pintype "output"))
    )
    (net (code "6") (name "/NEUTRAL") (class "Default")
      (node (ref "N") (pin "1") (pinfunction "1_1") (pintype "passive"))
      (node (ref "R9") (pin "2") (pinfunction "2_2") (pintype "passive"))
      (node (ref "U1") (pin "16") (pinfunction "PC6_(HS)/SPI_MOSI_[TIM1_CH1]_16") (pintype "passive"))
      (node (ref "U4") (pin "2") (pinfunction "Q_2") (pintype "output"))
    )
    (net (code "7") (name "/REVERSE") (class "Default")
      (node (ref "R") (pin "1") (pinfunction "1_1") (pintype "passive"))
      (node (ref "R3") (pin "2") (pinfunction "2_2") (pintype "passive"))
      (node (ref "U1") (pin "13") (pinfunction "PC3_(HS)/TIM1_CH3_[TLI][TIM1_CH1N]_13") (pintype "passive"))
      (node (ref "U2") (pin "2") (pinfunction "Q_2") (pintype "output"))
    )
    (net (code "8") (name "/S1") (class "Default")
      (node (ref "U1") (pin "14") (pinfunction "PC4_(HS)/TIM1_CH4/CLK_CCO/AIN2_[TIM1_CH2N]_14") (pintype "passive"))
      (node (ref "U10") (pin "2") (pinfunction "G1_2") (pintype "passive"))
    )
    (net (code "9") (name "/S2") (class "Default")
      (node (ref "R27") (pin "1") (pinfunction "1_1") (pintype "passive"))
      (node (ref "U1") (pin "11") (pinfunction "PB5_(T)/I2C_SDA_[TIM1_BKIN]_11") (pintype "passive"))
      (node (ref "U10") (pin "5") (pinfunction "G2_5") (pintype "passive"))
    )
    (net (code "10") (name "/S3") (class "Default")
      (node (ref "R28") (pin "1") (pinfunction "1_1") (pintype "passive"))
      (node (ref "U1") (pin "12") (pinfunction "PB4_(T)/I2C_SCL_[ADC_ETR]_12") (pintype "passive"))
      (node (ref "U9") (pin "5") (pinfunction "G2_5") (pintype "passive"))
    )
    (net (code "11") (name "/S4") (class "Default")
      (node (ref "U1") (pin "15") (pinfunction "PC5_(HS)/SPI_SCK_[TIM5_CH1]_15") (pintype "passive"))
      (node (ref "U9") (pin "2") (pinfunction "G1_2") (pintype "passive"))
    )
    (net (code "12") (name "/SIGNAL1") (class "Default")
      (node (ref "A1") (pin "1") (pinfunction "1_1") (pintype "passive"))
      (node (ref "C23") (pin "2") (pinfunction "2_2") (pintype "passive"))
      (node (ref "D11") (pin "2") (pinfunction "CATHODE_2") (pintype "passive"))
      (node (ref "J3") (pin "4") (pinfunction "4_4") (pintype "passive"))
      (node (ref "R24") (pin "2") (pinfunction "2_2") (pintype "passive"))
      (node (ref "R26") (pin "1") (pinfunction "1_1") (pintype "passive"))
    )
    (net (code "13") (name "/SIGNAL2") (class "Default")
      (node (ref "A2") (pin "1") (pinfunction "1_1") (pintype "passive"))
      (node (ref "C21") (pin "2") (pinfunction "2_2") (pintype "passive"))
      (node (ref "D5") (pin "2") (pinfunction "CATHODE_2") (pintype "passive"))
      (node (ref "J3") (pin "5") (pinfunction "5_5") (pintype "passive"))
      (node (ref "R18") (pin "2") (pinfunction "2_2") (pintype "passive"))
      (node (ref "R20") (pin "1") (pinfunction "1_1") (pintype "passive"))
    )
    (net (code "14") (name "/SIGNAL3") (class "Default")
      (node (ref "A3") (pin "1") (pinfunction "1_1") (pintype "passive"))
      (node (ref "C20") (pin "2") (pinfunction "2_2") (pintype "passive"))
      (node (ref "D4") (pin "2") (pinfunction "CATHODE_2") (pintype "passive"))
      (node (ref "J3") (pin "6") (pinfunction "6_6") (pintype "passive"))
      (node (ref "R17") (pin "2") (pinfunction "2_2") (pintype "passive"))
      (node (ref "R19") (pin "1") (pinfunction "1_1") (pintype "passive"))
    )
    (net (code "15") (name "/SIGNAL4") (class "Default")
      (node (ref "A4") (pin "1") (pinfunction "1_1") (pintype "passive"))
      (node (ref "C22") (pin "2") (pinfunction "2_2") (pintype "passive"))
      (node (ref "D10") (pin "2") (pinfunction "CATHODE_2") (pintype "passive"))
      (node (ref "J3") (pin "2") (pinfunction "2_2") (pintype "passive"))
      (node (ref "R23") (pin "2") (pinfunction "2_2") (pintype "passive"))
      (node (ref "R25") (pin "1") (pinfunction "1_1") (pintype "passive"))
    )
    (net (code "16") (name "/SWIM") (class "Default")
      (node (ref "D12") (pin "2") (pinfunction "CATHODE_2") (pintype "passive"))
      (node (ref "J1") (pin "5") (pinfunction "5_5") (pintype "passive"))
      (node (ref "U1") (pin "18") (pinfunction "PD1_(HS)/SWIM_18") (pintype "passive"))
    )
    (net (code "17") (name "/UART_RX") (class "Default")
      (node (ref "D14") (pin "2") (pinfunction "CATHODE_2") (pintype "passive"))
      (node (ref "J1") (pin "4") (pinfunction "4_4") (pintype "passive"))
      (node (ref "U1") (pin "3") (pinfunction "PD6_(HS)/AIN6/LINUART_RX_3") (pintype "passive"))
    )
    (net (code "18") (name "/UART_TX") (class "Default")
      (node (ref "D13") (pin "2") (pinfunction "CATHODE_2") (pintype "passive"))
      (node (ref "J1") (pin "6") (pinfunction "6_6") (pintype "passive"))
      (node (ref "U1") (pin "2") (pinfunction "PD5_(HS)/AIN5/LINUART_TX_2") (pintype "passive"))
    )
    (net (code "19") (name "/nRESET") (class "Default")
      (node (ref "C6") (pin "1") (pinfunction "1_1") (pintype "passive"))
      (node (ref "R5") (pin "1") (pinfunction "1_1") (pintype "passive"))
      (node (ref "R6") (pin "2") (pinfunction "2_2") (pintype "passive"))
      (node (ref "U1") (pin "4") (pinfunction "NRST_4") (pintype "passive"))
    )
    (net (code "20") (name "GND") (class "Default")
      (node (ref "C1") (pin "2") (pinfunction "2_2") (pintype "passive"))
      (node (ref "C10") (pin "1") (pinfunction "1_1") (pintype "passive"))
      (node (ref "C11") (pin "1") (pinfunction "1_1") (pintype "passive"))
      (node (ref "C12") (pin "2") (pinfunction "2_2") (pintype "passive"))
      (node (ref "C14") (pin "1") (pinfunction "1_1") (pintype "passive"))
      (node (ref "C15") (pin "2") (pinfunction "2_2") (pintype "passive"))
      (node (ref "C18") (pin "2") (pinfunction "2_2") (pintype "passive"))
      (node (ref "C19") (pin "1") (pinfunction "1_1") (pintype "passive"))
      (node (ref "C2") (pin "1") (pinfunction "1_1") (pintype "passive"))
      (node (ref "C20") (pin "1") (pinfunction "1_1") (pintype "passive"))
      (node (ref "C21") (pin "1") (pinfunction "1_1") (pintype "passive"))
      (node (ref "C22") (pin "1") (pinfunction "1_1") (pintype "passive"))
      (node (ref "C23") (pin "1") (pinfunction "1_1") (pintype "passive"))
      (node (ref "C24") (pin "2") (pinfunction "2_2") (pintype "passive"))
      (node (ref "C25") (pin "2") (pinfunction "2_2") (pintype "passive"))
      (node (ref "C26") (pin "2") (pinfunction "2_2") (pintype "passive"))
      (node (ref "C3") (pin "2") (pinfunction "2_2") (pintype "passive"))
      (node (ref "C4") (pin "1") (pinfunction "1_1") (pintype "passive"))
      (node (ref "C5") (pin "1") (pinfunction "1_1") (pintype "passive"))
      (node (ref "C6") (pin "2") (pinfunction "2_2") (pintype "passive"))
      (node (ref "C7") (pin "1") (pinfunction "1_1") (pintype "passive"))
      (node (ref "C8") (pin "1") (pinfunction "1_1") (pintype "passive"))
      (node (ref "C9") (pin "1") (pinfunction "1_1") (pintype "passive"))
      (node (ref "D1") (pin "1") (pinfunction "Cathode_1") (pintype "passive"))
      (node (ref "D10") (pin "1") (pinfunction "ANODE_1") (pintype "passive"))
      (node (ref "D11") (pin "1") (pinfunction "ANODE_1") (pintype "passive"))
      (node (ref "D12") (pin "1") (pinfunction "ANODE_1") (pintype "passive"))
      (node (ref "D13") (pin "1") (pinfunction "ANODE_1") (pintype "passive"))
      (node (ref "D14") (pin "1") (pinfunction "ANODE_1") (pintype "passive"))
      (node (ref "D15") (pin "1") (pinfunction "ANODE_1") (pintype "passive"))
      (node (ref "D4") (pin "1") (pinfunction "ANODE_1") (pintype "passive"))
      (node (ref "D5") (pin "1") (pinfunction "ANODE_1") (pintype "passive"))
      (node (ref "D7") (pin "1") (pinfunction "ANODE_1") (pintype "passive"))
      (node (ref "GND") (pin "1") (pinfunction "1_1") (pintype "passive"))
      (node (ref "J1") (pin "1") (pinfunction "1_1") (pintype "passive"))
      (node (ref "J3") (pin "1") (pinfunction "1_1") (pintype "passive"))
      (node (ref "R16") (pin "1") (pinfunction "1_1") (pintype "passive"))
      (node (ref "R19") (pin "2") (pinfunction "2_2") (pintype "passive"))
      (node (ref "R20") (pin "2") (pinfunction "2_2") (pintype "passive"))
      (node (ref "R25") (pin "2") (pinfunction "2_2") (pintype "passive"))
      (node (ref "R26") (pin "2") (pinfunction "2_2") (pintype "passive"))
      (node (ref "R30") (pin "1") (pinfunction "1_1") (pintype "passive"))
      (node (ref "U1") (pin "7") (pinfunction "VSS_7") (pintype "passive"))
      (node (ref "U2") (pin "3") (pinfunction "GND_3") (pintype "power_in"))
      (node (ref "U3") (pin "3") (pinfunction "GND_3") (pintype "power_in"))
      (node (ref "U4") (pin "3") (pinfunction "GND_3") (pintype "power_in"))
      (node (ref "U5") (pin "3") (pinfunction "GND_3") (pintype "power_in"))
      (node (ref "U6") (pin "3") (pinfunction "GND_3") (pintype "power_in"))
      (node (ref "U7") (pin "3") (pinfunction "GND_3") (pintype "power_in"))
      (node (ref "U8") (pin "1") (pinfunction "SYNC_1") (pintype "passive"))
      (node (ref "U8") (pin "2") (pinfunction "GND_2") (pintype "passive"))
      (node (ref "U8") (pin "9") (pinfunction "EPAD_9") (pintype "passive"))
    )
    (net (code "21") (name "Net-(C13-Pad2)") (class "Default")
      (node (ref "C13") (pin "2") (pinfunction "2_2") (pintype "passive"))
      (node (ref "R16") (pin "2") (pinfunction "2_2") (pintype "passive"))
    )
    (net (code "22") (name "Net-(D1-Anode)") (class "Default")
      (node (ref "C16") (pin "2") (pinfunction "2_2") (pintype "passive"))
      (node (ref "D1") (pin "2") (pinfunction "Anode_2") (pintype "passive"))
      (node (ref "L1") (pin "1") (pinfunction "1_1") (pintype "passive"))
      (node (ref "U8") (pin "6") (pinfunction "BUO_6") (pintype "passive"))
    )
    (net (code "23") (name "Net-(D2-ANODE)") (class "Default")
      (node (ref "D2") (pin "2") (pinfunction "ANODE_2") (pintype "passive"))
      (node (ref "U9") (pin "3") (pinfunction "D2_3") (pintype "passive"))
    )
    (net (code "24") (name "Net-(D2-CATHODE)") (class "Default")
      (node (ref "D2") (pin "1") (pinfunction "CATHODE_1") (pintype "passive"))
      (node (ref "R17") (pin "1") (pinfunction "1_1") (pintype "passive"))
    )
    (net (code "25") (name "Net-(D3-ANODE)") (class "Default")
      (node (ref "D3") (pin "2") (pinfunction "ANODE_2") (pintype "passive"))
      (node (ref "U10") (pin "3") (pinfunction "D2_3") (pintype "passive"))
    )
    (net (code "26") (name "Net-(D3-CATHODE)") (class "Default")
      (node (ref "D3") (pin "1") (pinfunction "CATHODE_1") (pintype "passive"))
      (node (ref "R18") (pin "1") (pinfunction "1_1") (pintype "passive"))
    )
    (net (code "27") (name "Net-(D6-Anode)") (class "Default")
      (node (ref "D6") (pin "2") (pinfunction "Anode_2") (pintype "passive"))
      (node (ref "D7") (pin "2") (pinfunction "CATHODE_2") (pintype "passive"))
      (node (ref "J3") (pin "3") (pinfunction "3_3") (pintype "passive"))
    )
    (net (code "28") (name "Net-(D8-ANODE)") (class "Default")
      (node (ref "D8") (pin "2") (pinfunction "ANODE_2") (pintype "passive"))
      (node (ref "U9") (pin "6") (pinfunction "D1_6") (pintype "passive"))
    )
    (net (code "29") (name "Net-(D8-CATHODE)") (class "Default")
      (node (ref "D8") (pin "1") (pinfunction "CATHODE_1") (pintype "passive"))
      (node (ref "R23") (pin "1") (pinfunction "1_1") (pintype "passive"))
    )
    (net (code "30") (name "Net-(D9-ANODE)") (class "Default")
      (node (ref "D9") (pin "2") (pinfunction "ANODE_2") (pintype "passive"))
      (node (ref "U10") (pin "6") (pinfunction "D1_6") (pintype "passive"))
    )
    (net (code "31") (name "Net-(D9-CATHODE)") (class "Default")
      (node (ref "D9") (pin "1") (pinfunction "CATHODE_1") (pintype "passive"))
      (node (ref "R24") (pin "1") (pinfunction "1_1") (pintype "passive"))
    )
    (net (code "32") (name "Net-(D15-CATHODE)") (class "Default")
      (node (ref "D15") (pin "2") (pinfunction "CATHODE_2") (pintype "passive"))
      (node (ref "J1") (pin "3") (pinfunction "3_3") (pintype "passive"))
      (node (ref "R6") (pin "1") (pinfunction "1_1") (pintype "passive"))
    )
    (net (code "33") (name "Net-(U1-VCAP)") (class "Default")
      (node (ref "C3") (pin "1") (pinfunction "1_1") (pintype "passive"))
      (node (ref "U1") (pin "8") (pinfunction "VCAP_8") (pintype "passive"))
    )
    (net (code "34") (name "Net-(U2-VDD)") (class "Default")
      (node (ref "C4") (pin "2") (pinfunction "2_2") (pintype "passive"))
      (node (ref "R1") (pin "2") (pinfunction "2_2") (pintype "passive"))
      (node (ref "U2") (pin "1") (pinfunction "VDD_1") (pintype "power_in"))
    )
    (net (code "35") (name "Net-(U3-VDD)") (class "Default")
      (node (ref "C5") (pin "2") (pinfunction "2_2") (pintype "passive"))
      (node (ref "R2") (pin "2") (pinfunction "2_2") (pintype "passive"))
      (node (ref "U3") (pin "1") (pinfunction "VDD_1") (pintype "power_in"))
    )
    (net (code "36") (name "Net-(U4-VDD)") (class "Default")
      (node (ref "C7") (pin "2") (pinfunction "2_2") (pintype "passive"))
      (node (ref "R7") (pin "2") (pinfunction "2_2") (pintype "passive"))
      (node (ref "U4") (pin "1") (pinfunction "VDD_1") (pintype "power_in"))
    )
    (net (code "37") (name "Net-(U5-VDD)") (class "Default")
      (node (ref "C8") (pin "2") (pinfunction "2_2") (pintype "passive"))
      (node (ref "R8") (pin "2") (pinfunction "2_2") (pintype "passive"))
      (node (ref "U5") (pin "1") (pinfunction "VDD_1") (pintype "power_in"))
    )
    (net (code "38") (name "Net-(U6-VDD)") (class "Default")
      (node (ref "C9") (pin "2") (pinfunction "2_2") (pintype "passive"))
      (node (ref "R11") (pin "2") (pinfunction "2_2") (pintype "passive"))
      (node (ref "U6") (pin "1") (pinfunction "VDD_1") (pintype "power_in"))
    )
    (net (code "39") (name "Net-(U7-VDD)") (class "Default")
      (node (ref "C10") (pin "2") (pinfunction "2_2") (pintype "passive"))
      (node (ref "R12") (pin "2") (pinfunction "2_2") (pintype "passive"))
      (node (ref "U7") (pin "1") (pinfunction "VDD_1") (pintype "power_in"))
    )
    (net (code "40") (name "Net-(U8-BDS)") (class "Default")
      (node (ref "C16") (pin "1") (pinfunction "1_1") (pintype "passive"))
      (node (ref "U8") (pin "5") (pinfunction "BDS_5") (pintype "passive"))
    )
    (net (code "41") (name "Net-(U8-COMP)") (class "Default")
      (node (ref "C13") (pin "1") (pinfunction "1_1") (pintype "passive"))
      (node (ref "C24") (pin "1") (pinfunction "1_1") (pintype "passive"))
      (node (ref "U8") (pin "3") (pinfunction "COMP_3") (pintype "passive"))
    )
    (net (code "42") (name "Net-(U8-EN)") (class "Default")
      (node (ref "R15") (pin "1") (pinfunction "1_1") (pintype "passive"))
      (node (ref "U8") (pin "7") (pinfunction "EN_7") (pintype "passive"))
    )
    (net (code "43") (name "Net-(U8-FB)") (class "Default")
      (node (ref "C14") (pin "2") (pinfunction "2_2") (pintype "passive"))
      (node (ref "C19") (pin "2") (pinfunction "2_2") (pintype "passive"))
      (node (ref "FB1") (pin "1") (pinfunction "1_1") (pintype "passive"))
      (node (ref "L1") (pin "2") (pinfunction "2_2") (pintype "passive"))
      (node (ref "U8") (pin "4") (pinfunction "FB_4") (pintype "passive"))
    )
    (net (code "44") (name "VCC_5V") (class "Default")
      (node (ref "5V") (pin "1") (pinfunction "1_1") (pintype "passive"))
      (node (ref "C1") (pin "1") (pinfunction "1_1") (pintype "passive"))
      (node (ref "C15") (pin "1") (pinfunction "1_1") (pintype "passive"))
      (node (ref "C2") (pin "2") (pinfunction "2_2") (pintype "passive"))
      (node (ref "C25") (pin "1") (pinfunction "1_1") (pintype "passive"))
      (node (ref "C26") (pin "1") (pinfunction "1_1") (pintype "passive"))
      (node (ref "FB1") (pin "2") (pinfunction "2_2") (pintype "passive"))
      (node (ref "J1") (pin "2") (pinfunction "2_2") (pintype "power_in"))
      (node (ref "R1") (pin "1") (pinfunction "1_1") (pintype "passive"))
      (node (ref "R10") (pin "1") (pinfunction "1_1") (pintype "passive"))
      (node (ref "R11") (pin "1") (pinfunction "1_1") (pintype "passive"))
      (node (ref "R12") (pin "1") (pinfunction "1_1") (pintype "passive"))
      (node (ref "R13") (pin "1") (pinfunction "1_1") (pintype "passive"))
      (node (ref "R14") (pin "1") (pinfunction "1_1") (pintype "passive"))
      (node (ref "R2") (pin "1") (pinfunction "1_1") (pintype "passive"))
      (node (ref "R27") (pin "2") (pinfunction "2_2") (pintype "passive"))
      (node (ref "R28") (pin "2") (pinfunction "2_2") (pintype "passive"))
      (node (ref "R29") (pin "2") (pinfunction "2_2") (pintype "passive"))
      (node (ref "R3") (pin "1") (pinfunction "1_1") (pintype "passive"))
      (node (ref "R4") (pin "1") (pinfunction "1_1") (pintype "passive"))
      (node (ref "R5") (pin "2") (pinfunction "2_2") (pintype "passive"))
      (node (ref "R7") (pin "1") (pinfunction "1_1") (pintype "passive"))
      (node (ref "R8") (pin "1") (pinfunction "1_1") (pintype "passive"))
      (node (ref "R9") (pin "1") (pinfunction "1_1") (pintype "passive"))
      (node (ref "U1") (pin "9") (pinfunction "VDD_9") (pintype "passive"))
      (node (ref "U10") (pin "1") (pinfunction "S1_1") (pintype "passive"))
      (node (ref "U10") (pin "4") (pinfunction "S2_4") (pintype "passive"))
      (node (ref "U9") (pin "1") (pinfunction "S1_1") (pintype "passive"))
      (node (ref "U9") (pin "4") (pinfunction "S2_4") (pintype "passive"))
    )
    (net (code "45") (name "VCC_IN") (class "Default")
      (node (ref "C11") (pin "2") (pinfunction "2_2") (pintype "passive"))
      (node (ref "C12") (pin "1") (pinfunction "1_1") (pintype "passive"))
      (node (ref "C18") (pin "1") (pinfunction "1_1") (pintype "passive"))
      (node (ref "D6") (pin "1") (pinfunction "Cathode_1") (pintype "passive"))
      (node (ref "R15") (pin "2") (pinfunction "2_2") (pintype "passive"))
      (node (ref "U8") (pin "8") (pinfunction "VS_8") (pintype "passive"))
    )
    (net (code "46") (name "unconnected-(FID1-Pad0)") (class "Default")
      (node (ref "FID1") (pin "0") (pinfunction "0_0") (pintype "passive+no_connect"))
    )
    (net (code "47") (name "unconnected-(FID2-Pad0)") (class "Default")
      (node (ref "FID2") (pin "0") (pinfunction "0_0") (pintype "passive+no_connect"))
    )
    (net (code "48") (name "unconnected-(FID3-Pad0)") (class "Default")
      (node (ref "FID3") (pin "0") (pinfunction "0_0") (pintype "passive+no_connect"))
    )
    (net (code "49") (name "unconnected-(FID4-Pad0)") (class "Default")
      (node (ref "FID4") (pin "0") (pinfunction "0_0") (pintype "passive+no_connect"))
    )
    (net (code "50") (name "unconnected-(U1-PA1{slash}OSCIN-Pad5)") (class "Default")
      (node (ref "U1") (pin "5") (pinfunction "PA1/OSCIN_5") (pintype "passive+no_connect"))
    )
    (net (code "51") (name "unconnected-(U1-PA2{slash}OSCOUT-Pad6)") (class "Default")
      (node (ref "U1") (pin "6") (pinfunction "PA2/OSCOUT_6") (pintype "passive+no_connect"))
    )
  )
)
